# Main.net
KiCad netlist of a schematic drawn in Altium Designer
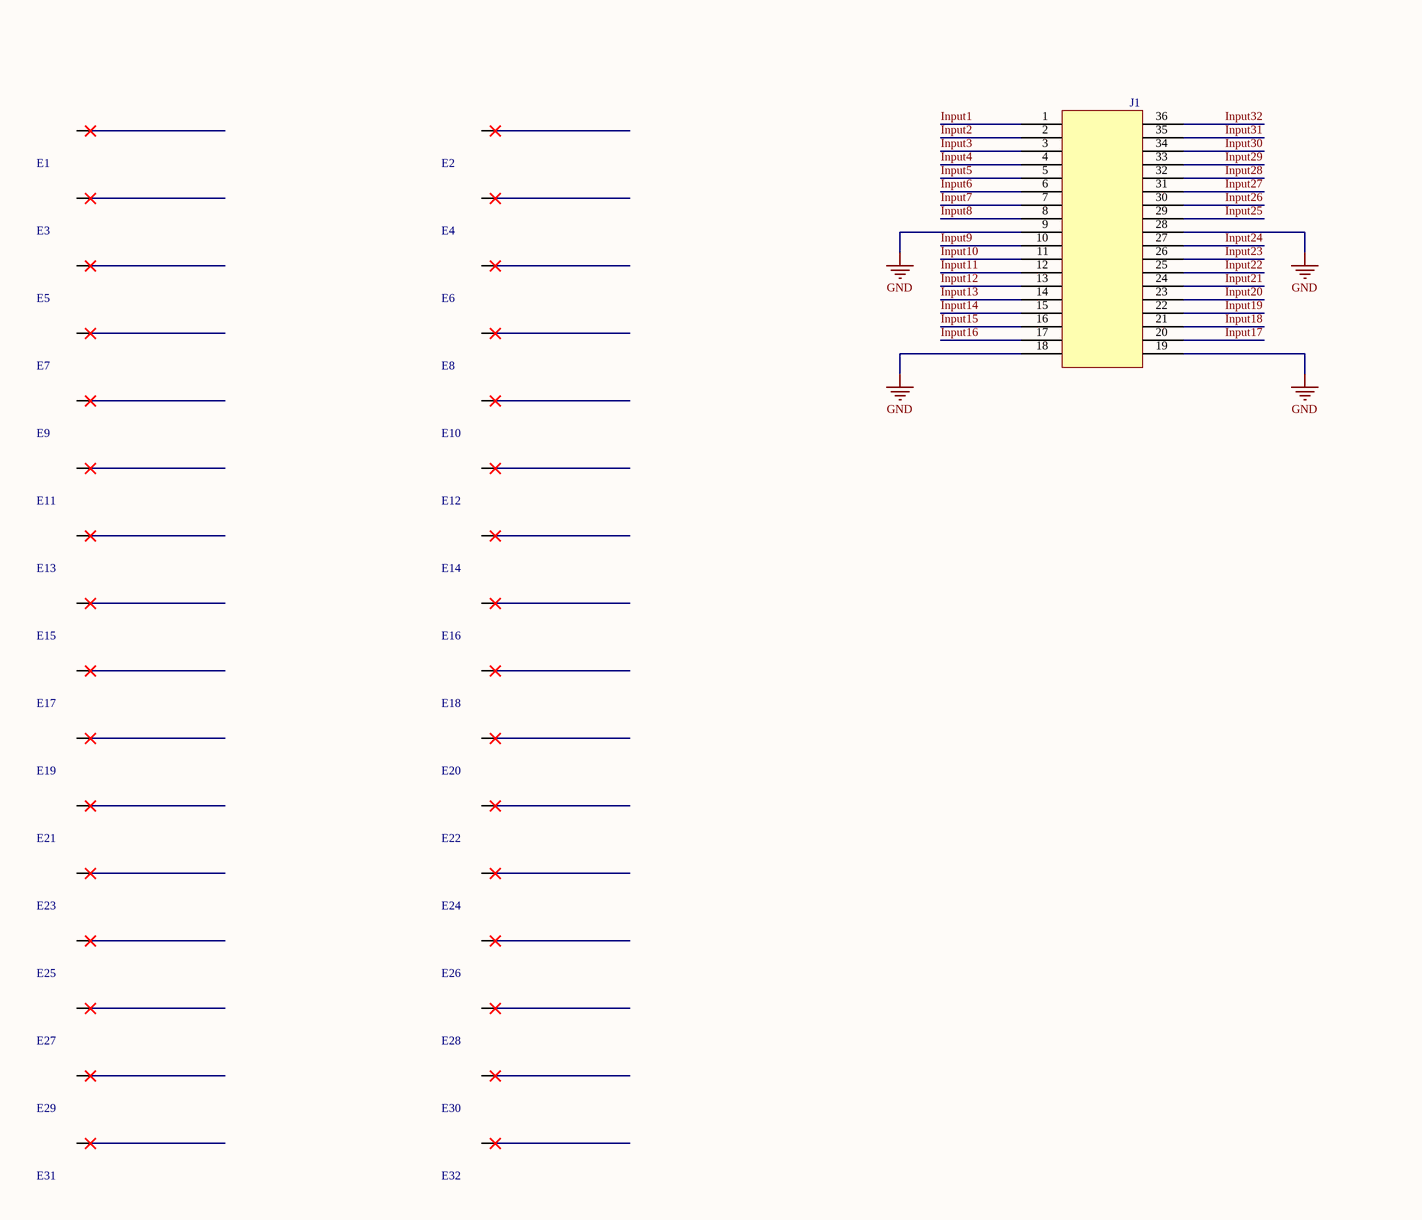
[diagram p0: Main.SchDoc, left]
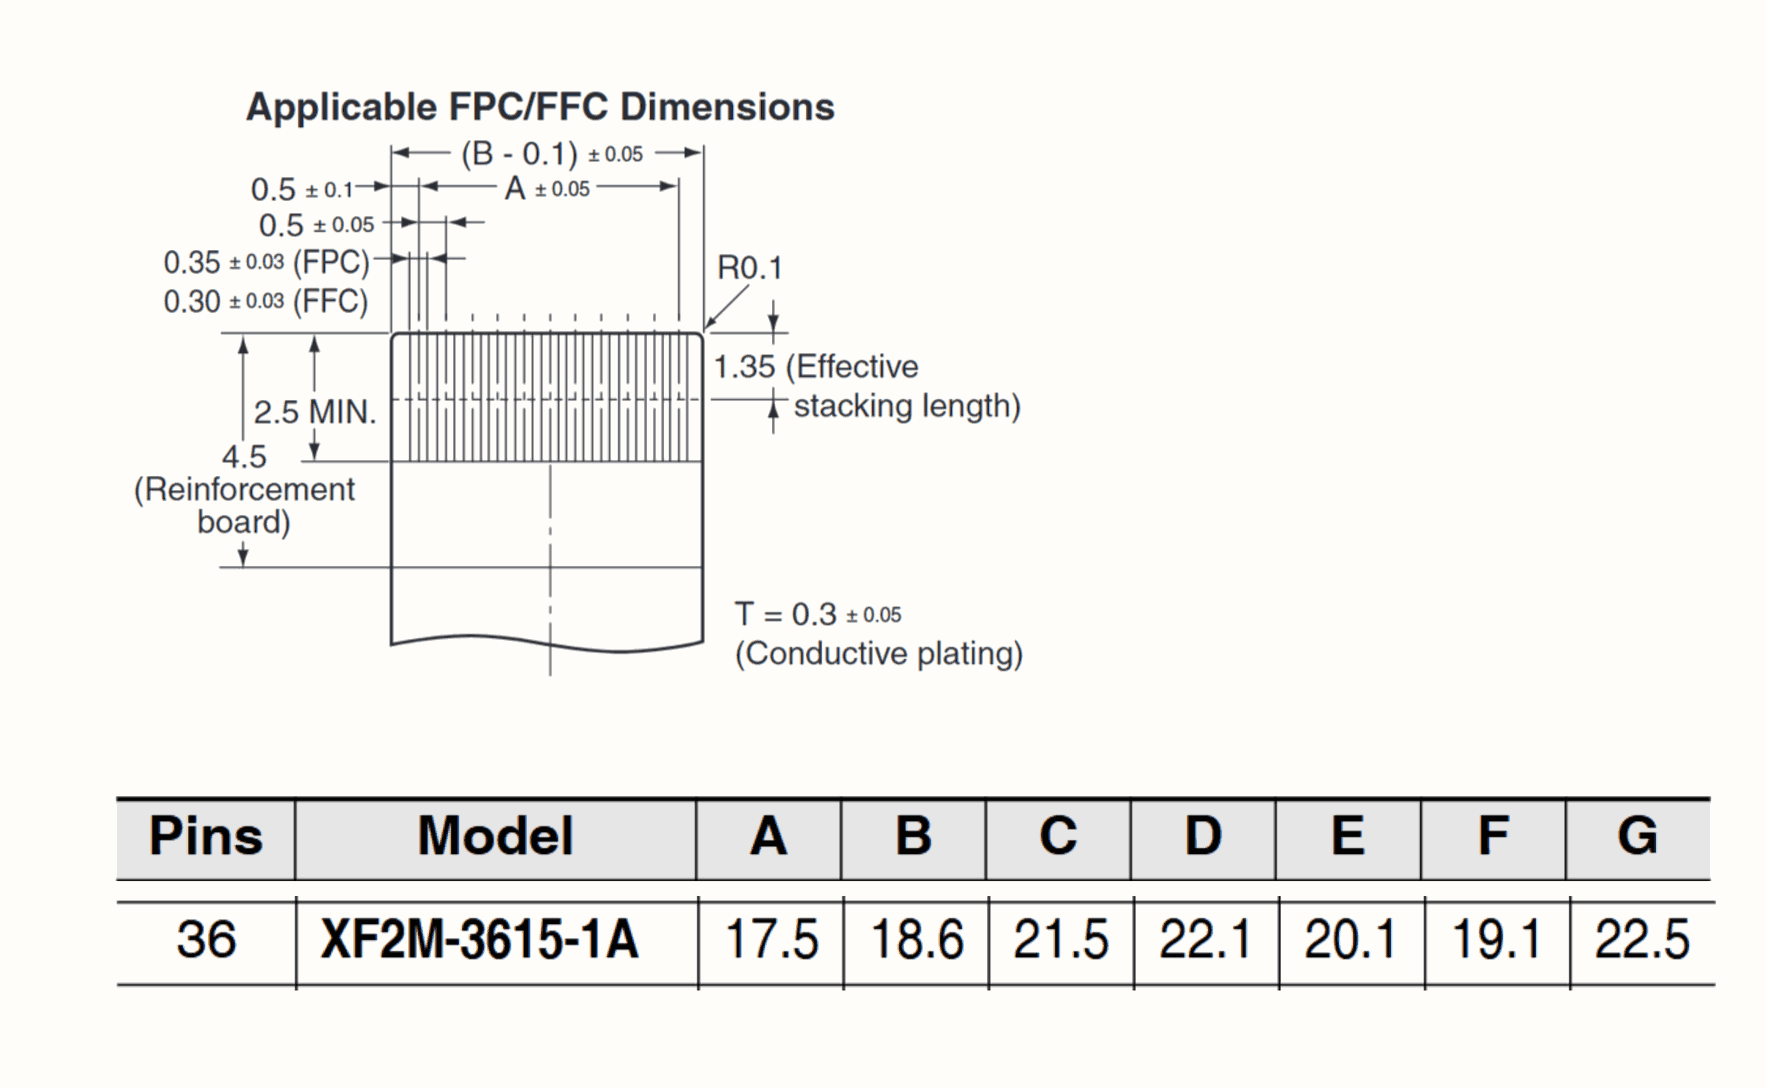
[diagram p1: Main.SchDoc, right]

(export (version "E")
  (design (tool "Eeschema 10.0.6"))
  (components
    (comp (ref "E1")
      (value "2.5 mm")
      (footprint "PCBComponent_1")
      (description "Microneedle electrode - 2.5 mm diameter")
      (libsource (lib "Miscellaneous") (part "SENSE_UNEEDLE"))
    )
    (comp (ref "E2")
      (value "2.5 mm")
      (footprint "PCBComponent_1")
      (description "Microneedle electrode - 2.5 mm diameter")
      (libsource (lib "Miscellaneous") (part "SENSE_UNEEDLE"))
    )
    (comp (ref "E3")
      (value "2.5 mm")
      (footprint "PCBComponent_1")
      (description "Microneedle electrode - 2.5 mm diameter")
      (libsource (lib "Miscellaneous") (part "SENSE_UNEEDLE"))
    )
    (comp (ref "E4")
      (value "2.5 mm")
      (footprint "PCBComponent_1")
      (description "Microneedle electrode - 2.5 mm diameter")
      (libsource (lib "Miscellaneous") (part "SENSE_UNEEDLE"))
    )
    (comp (ref "E5")
      (value "2.5 mm")
      (footprint "PCBComponent_1")
      (description "Microneedle electrode - 2.5 mm diameter")
      (libsource (lib "Miscellaneous") (part "SENSE_UNEEDLE"))
    )
    (comp (ref "E6")
      (value "2.5 mm")
      (footprint "PCBComponent_1")
      (description "Microneedle electrode - 2.5 mm diameter")
      (libsource (lib "Miscellaneous") (part "SENSE_UNEEDLE"))
    )
    (comp (ref "E7")
      (value "2.5 mm")
      (footprint "PCBComponent_1")
      (description "Microneedle electrode - 2.5 mm diameter")
      (libsource (lib "Miscellaneous") (part "SENSE_UNEEDLE"))
    )
    (comp (ref "E8")
      (value "2.5 mm")
      (footprint "PCBComponent_1")
      (description "Microneedle electrode - 2.5 mm diameter")
      (libsource (lib "Miscellaneous") (part "SENSE_UNEEDLE"))
    )
    (comp (ref "E9")
      (value "2.5 mm")
      (footprint "PCBComponent_1")
      (description "Microneedle electrode - 2.5 mm diameter")
      (libsource (lib "Miscellaneous") (part "SENSE_UNEEDLE"))
    )
    (comp (ref "E10")
      (value "2.5 mm")
      (footprint "PCBComponent_1")
      (description "Microneedle electrode - 2.5 mm diameter")
      (libsource (lib "Miscellaneous") (part "SENSE_UNEEDLE"))
    )
    (comp (ref "E11")
      (value "2.5 mm")
      (footprint "PCBComponent_1")
      (description "Microneedle electrode - 2.5 mm diameter")
      (libsource (lib "Miscellaneous") (part "SENSE_UNEEDLE"))
    )
    (comp (ref "E12")
      (value "2.5 mm")
      (footprint "PCBComponent_1")
      (description "Microneedle electrode - 2.5 mm diameter")
      (libsource (lib "Miscellaneous") (part "SENSE_UNEEDLE"))
    )
    (comp (ref "E13")
      (value "2.5 mm")
      (footprint "PCBComponent_1")
      (description "Microneedle electrode - 2.5 mm diameter")
      (libsource (lib "Miscellaneous") (part "SENSE_UNEEDLE"))
    )
    (comp (ref "E14")
      (value "2.5 mm")
      (footprint "PCBComponent_1")
      (description "Microneedle electrode - 2.5 mm diameter")
      (libsource (lib "Miscellaneous") (part "SENSE_UNEEDLE"))
    )
    (comp (ref "E15")
      (value "2.5 mm")
      (footprint "PCBComponent_1")
      (description "Microneedle electrode - 2.5 mm diameter")
      (libsource (lib "Miscellaneous") (part "SENSE_UNEEDLE"))
    )
    (comp (ref "E16")
      (value "2.5 mm")
      (footprint "PCBComponent_1")
      (description "Microneedle electrode - 2.5 mm diameter")
      (libsource (lib "Miscellaneous") (part "SENSE_UNEEDLE"))
    )
    (comp (ref "E17")
      (value "2.5 mm")
      (footprint "PCBComponent_1")
      (description "Microneedle electrode - 2.5 mm diameter")
      (libsource (lib "Miscellaneous") (part "SENSE_UNEEDLE"))
    )
    (comp (ref "E18")
      (value "2.5 mm")
      (footprint "PCBComponent_1")
      (description "Microneedle electrode - 2.5 mm diameter")
      (libsource (lib "Miscellaneous") (part "SENSE_UNEEDLE"))
    )
    (comp (ref "E19")
      (value "2.5 mm")
      (footprint "PCBComponent_1")
      (description "Microneedle electrode - 2.5 mm diameter")
      (libsource (lib "Miscellaneous") (part "SENSE_UNEEDLE"))
    )
    (comp (ref "E20")
      (value "2.5 mm")
      (footprint "PCBComponent_1")
      (description "Microneedle electrode - 2.5 mm diameter")
      (libsource (lib "Miscellaneous") (part "SENSE_UNEEDLE"))
    )
    (comp (ref "E21")
      (value "2.5 mm")
      (footprint "PCBComponent_1")
      (description "Microneedle electrode - 2.5 mm diameter")
      (libsource (lib "Miscellaneous") (part "SENSE_UNEEDLE"))
    )
    (comp (ref "E22")
      (value "2.5 mm")
      (footprint "PCBComponent_1")
      (description "Microneedle electrode - 2.5 mm diameter")
      (libsource (lib "Miscellaneous") (part "SENSE_UNEEDLE"))
    )
    (comp (ref "E23")
      (value "2.5 mm")
      (footprint "PCBComponent_1")
      (description "Microneedle electrode - 2.5 mm diameter")
      (libsource (lib "Miscellaneous") (part "SENSE_UNEEDLE"))
    )
    (comp (ref "E24")
      (value "2.5 mm")
      (footprint "PCBComponent_1")
      (description "Microneedle electrode - 2.5 mm diameter")
      (libsource (lib "Miscellaneous") (part "SENSE_UNEEDLE"))
    )
    (comp (ref "E25")
      (value "2.5 mm")
      (footprint "PCBComponent_1")
      (description "Microneedle electrode - 2.5 mm diameter")
      (libsource (lib "Miscellaneous") (part "SENSE_UNEEDLE"))
    )
    (comp (ref "E26")
      (value "2.5 mm")
      (footprint "PCBComponent_1")
      (description "Microneedle electrode - 2.5 mm diameter")
      (libsource (lib "Miscellaneous") (part "SENSE_UNEEDLE"))
    )
    (comp (ref "E27")
      (value "2.5 mm")
      (footprint "PCBComponent_1")
      (description "Microneedle electrode - 2.5 mm diameter")
      (libsource (lib "Miscellaneous") (part "SENSE_UNEEDLE"))
    )
    (comp (ref "E28")
      (value "2.5 mm")
      (footprint "PCBComponent_1")
      (description "Microneedle electrode - 2.5 mm diameter")
      (libsource (lib "Miscellaneous") (part "SENSE_UNEEDLE"))
    )
    (comp (ref "E29")
      (value "2.5 mm")
      (footprint "PCBComponent_1")
      (description "Microneedle electrode - 2.5 mm diameter")
      (libsource (lib "Miscellaneous") (part "SENSE_UNEEDLE"))
    )
    (comp (ref "E30")
      (value "2.5 mm")
      (footprint "PCBComponent_1")
      (description "Microneedle electrode - 2.5 mm diameter")
      (libsource (lib "Miscellaneous") (part "SENSE_UNEEDLE"))
    )
    (comp (ref "E31")
      (value "2.5 mm")
      (footprint "PCBComponent_1")
      (description "Microneedle electrode - 2.5 mm diameter")
      (libsource (lib "Miscellaneous") (part "SENSE_UNEEDLE"))
    )
    (comp (ref "E32")
      (value "2.5 mm")
      (footprint "PCBComponent_1")
      (description "Microneedle electrode - 2.5 mm diameter")
      (libsource (lib "Miscellaneous") (part "SENSE_UNEEDLE"))
    )
    (comp (ref "J1")
      (value "XF2M-3615-1A")
      (footprint "CONN_FPC_2X18_0MM5")
      (description "FPC Connector - FPC Side. 0.5 mm pitch\r\nCompatible with XF2M-3615-1A")
      (libsource (lib "Connectors") (part "CONN_FPC_2X18_0MM5"))
    )
  )
  (nets
    (net (code "1") (name "/Input1") (class "Default")
      (node (ref "J1") (pin "1") (pinfunction "1_1") (pintype "passive"))
    )
    (net (code "2") (name "/Input2") (class "Default")
      (node (ref "J1") (pin "2") (pinfunction "2_2") (pintype "passive"))
    )
    (net (code "3") (name "/Input3") (class "Default")
      (node (ref "J1") (pin "3") (pinfunction "3_3") (pintype "passive"))
    )
    (net (code "4") (name "/Input4") (class "Default")
      (node (ref "J1") (pin "4") (pinfunction "4_4") (pintype "passive"))
    )
    (net (code "5") (name "/Input5") (class "Default")
      (node (ref "J1") (pin "5") (pinfunction "5_5") (pintype "passive"))
    )
    (net (code "6") (name "/Input6") (class "Default")
      (node (ref "J1") (pin "6") (pinfunction "6_6") (pintype "passive"))
    )
    (net (code "7") (name "/Input7") (class "Default")
      (node (ref "J1") (pin "7") (pinfunction "7_7") (pintype "passive"))
    )
    (net (code "8") (name "/Input8") (class "Default")
      (node (ref "J1") (pin "8") (pinfunction "8_8") (pintype "passive"))
    )
    (net (code "9") (name "/Input9") (class "Default")
      (node (ref "J1") (pin "10") (pinfunction "10_10") (pintype "passive"))
    )
    (net (code "10") (name "/Input10") (class "Default")
      (node (ref "J1") (pin "11") (pinfunction "11_11") (pintype "passive"))
    )
    (net (code "11") (name "/Input11") (class "Default")
      (node (ref "J1") (pin "12") (pinfunction "12_12") (pintype "passive"))
    )
    (net (code "12") (name "/Input12") (class "Default")
      (node (ref "J1") (pin "13") (pinfunction "13_13") (pintype "passive"))
    )
    (net (code "13") (name "/Input13") (class "Default")
      (node (ref "J1") (pin "14") (pinfunction "14_14") (pintype "passive"))
    )
    (net (code "14") (name "/Input14") (class "Default")
      (node (ref "J1") (pin "15") (pinfunction "15_15") (pintype "passive"))
    )
    (net (code "15") (name "/Input15") (class "Default")
      (node (ref "J1") (pin "16") (pinfunction "16_16") (pintype "passive"))
    )
    (net (code "16") (name "/Input16") (class "Default")
      (node (ref "J1") (pin "17") (pinfunction "17_17") (pintype "passive"))
    )
    (net (code "17") (name "/Input17") (class "Default")
      (node (ref "J1") (pin "20") (pinfunction "20_20") (pintype "passive"))
    )
    (net (code "18") (name "/Input18") (class "Default")
      (node (ref "J1") (pin "21") (pinfunction "21_21") (pintype "passive"))
    )
    (net (code "19") (name "/Input19") (class "Default")
      (node (ref "J1") (pin "22") (pinfunction "22_22") (pintype "passive"))
    )
    (net (code "20") (name "/Input20") (class "Default")
      (node (ref "J1") (pin "23") (pinfunction "23_23") (pintype "passive"))
    )
    (net (code "21") (name "/Input21") (class "Default")
      (node (ref "J1") (pin "24") (pinfunction "24_24") (pintype "passive"))
    )
    (net (code "22") (name "/Input22") (class "Default")
      (node (ref "J1") (pin "25") (pinfunction "25_25") (pintype "passive"))
    )
    (net (code "23") (name "/Input23") (class "Default")
      (node (ref "J1") (pin "26") (pinfunction "26_26") (pintype "passive"))
    )
    (net (code "24") (name "/Input24") (class "Default")
      (node (ref "J1") (pin "27") (pinfunction "27_27") (pintype "passive"))
    )
    (net (code "25") (name "/Input25") (class "Default")
      (node (ref "J1") (pin "29") (pinfunction "29_29") (pintype "passive"))
    )
    (net (code "26") (name "/Input26") (class "Default")
      (node (ref "J1") (pin "30") (pinfunction "30_30") (pintype "passive"))
    )
    (net (code "27") (name "/Input27") (class "Default")
      (node (ref "J1") (pin "31") (pinfunction "31_31") (pintype "passive"))
    )
    (net (code "28") (name "/Input28") (class "Default")
      (node (ref "J1") (pin "32") (pinfunction "32_32") (pintype "passive"))
    )
    (net (code "29") (name "/Input29") (class "Default")
      (node (ref "J1") (pin "33") (pinfunction "33_33") (pintype "passive"))
    )
    (net (code "30") (name "/Input30") (class "Default")
      (node (ref "J1") (pin "34") (pinfunction "34_34") (pintype "passive"))
    )
    (net (code "31") (name "/Input31") (class "Default")
      (node (ref "J1") (pin "35") (pinfunction "35_35") (pintype "passive"))
    )
    (net (code "32") (name "/Input32") (class "Default")
      (node (ref "J1") (pin "36") (pinfunction "36_36") (pintype "passive"))
    )
    (net (code "33") (name "GND") (class "Default")
      (node (ref "J1") (pin "18") (pinfunction "18_18") (pintype "passive"))
      (node (ref "J1") (pin "19") (pinfunction "19_19") (pintype "passive"))
      (node (ref "J1") (pin "28") (pinfunction "28_28") (pintype "passive"))
      (node (ref "J1") (pin "9") (pinfunction "9_9") (pintype "passive"))
    )
    (net (code "34") (name "unconnected-(E1-E-Pad1)") (class "Default")
      (node (ref "E1") (pin "1") (pinfunction "E_1") (pintype "passive+no_connect"))
    )
    (net (code "35") (name "unconnected-(E2-E-Pad1)") (class "Default")
      (node (ref "E2") (pin "1") (pinfunction "E_1") (pintype "passive+no_connect"))
    )
    (net (code "36") (name "unconnected-(E3-E-Pad1)") (class "Default")
      (node (ref "E3") (pin "1") (pinfunction "E_1") (pintype "passive+no_connect"))
    )
    (net (code "37") (name "unconnected-(E4-E-Pad1)") (class "Default")
      (node (ref "E4") (pin "1") (pinfunction "E_1") (pintype "passive+no_connect"))
    )
    (net (code "38") (name "unconnected-(E5-E-Pad1)") (class "Default")
      (node (ref "E5") (pin "1") (pinfunction "E_1") (pintype "passive+no_connect"))
    )
    (net (code "39") (name "unconnected-(E6-E-Pad1)") (class "Default")
      (node (ref "E6") (pin "1") (pinfunction "E_1") (pintype "passive+no_connect"))
    )
    (net (code "40") (name "unconnected-(E7-E-Pad1)") (class "Default")
      (node (ref "E7") (pin "1") (pinfunction "E_1") (pintype "passive+no_connect"))
    )
    (net (code "41") (name "unconnected-(E8-E-Pad1)") (class "Default")
      (node (ref "E8") (pin "1") (pinfunction "E_1") (pintype "passive+no_connect"))
    )
    (net (code "42") (name "unconnected-(E9-E-Pad1)") (class "Default")
      (node (ref "E9") (pin "1") (pinfunction "E_1") (pintype "passive+no_connect"))
    )
    (net (code "43") (name "unconnected-(E10-E-Pad1)") (class "Default")
      (node (ref "E10") (pin "1") (pinfunction "E_1") (pintype "passive+no_connect"))
    )
    (net (code "44") (name "unconnected-(E11-E-Pad1)") (class "Default")
      (node (ref "E11") (pin "1") (pinfunction "E_1") (pintype "passive+no_connect"))
    )
    (net (code "45") (name "unconnected-(E12-E-Pad1)") (class "Default")
      (node (ref "E12") (pin "1") (pinfunction "E_1") (pintype "passive+no_connect"))
    )
    (net (code "46") (name "unconnected-(E13-E-Pad1)") (class "Default")
      (node (ref "E13") (pin "1") (pinfunction "E_1") (pintype "passive+no_connect"))
    )
    (net (code "47") (name "unconnected-(E14-E-Pad1)") (class "Default")
      (node (ref "E14") (pin "1") (pinfunction "E_1") (pintype "passive+no_connect"))
    )
    (net (code "48") (name "unconnected-(E15-E-Pad1)") (class "Default")
      (node (ref "E15") (pin "1") (pinfunction "E_1") (pintype "passive+no_connect"))
    )
    (net (code "49") (name "unconnected-(E16-E-Pad1)") (class "Default")
      (node (ref "E16") (pin "1") (pinfunction "E_1") (pintype "passive+no_connect"))
    )
    (net (code "50") (name "unconnected-(E17-E-Pad1)") (class "Default")
      (node (ref "E17") (pin "1") (pinfunction "E_1") (pintype "passive+no_connect"))
    )
    (net (code "51") (name "unconnected-(E18-E-Pad1)") (class "Default")
      (node (ref "E18") (pin "1") (pinfunction "E_1") (pintype "passive+no_connect"))
    )
    (net (code "52") (name "unconnected-(E19-E-Pad1)") (class "Default")
      (node (ref "E19") (pin "1") (pinfunction "E_1") (pintype "passive+no_connect"))
    )
    (net (code "53") (name "unconnected-(E20-E-Pad1)") (class "Default")
      (node (ref "E20") (pin "1") (pinfunction "E_1") (pintype "passive+no_connect"))
    )
    (net (code "54") (name "unconnected-(E21-E-Pad1)") (class "Default")
      (node (ref "E21") (pin "1") (pinfunction "E_1") (pintype "passive+no_connect"))
    )
    (net (code "55") (name "unconnected-(E22-E-Pad1)") (class "Default")
      (node (ref "E22") (pin "1") (pinfunction "E_1") (pintype "passive+no_connect"))
    )
    (net (code "56") (name "unconnected-(E23-E-Pad1)") (class "Default")
      (node (ref "E23") (pin "1") (pinfunction "E_1") (pintype "passive+no_connect"))
    )
    (net (code "57") (name "unconnected-(E24-E-Pad1)") (class "Default")
      (node (ref "E24") (pin "1") (pinfunction "E_1") (pintype "passive+no_connect"))
    )
    (net (code "58") (name "unconnected-(E25-E-Pad1)") (class "Default")
      (node (ref "E25") (pin "1") (pinfunction "E_1") (pintype "passive+no_connect"))
    )
    (net (code "59") (name "unconnected-(E26-E-Pad1)") (class "Default")
      (node (ref "E26") (pin "1") (pinfunction "E_1") (pintype "passive+no_connect"))
    )
    (net (code "60") (name "unconnected-(E27-E-Pad1)") (class "Default")
      (node (ref "E27") (pin "1") (pinfunction "E_1") (pintype "passive+no_connect"))
    )
    (net (code "61") (name "unconnected-(E28-E-Pad1)") (class "Default")
      (node (ref "E28") (pin "1") (pinfunction "E_1") (pintype "passive+no_connect"))
    )
    (net (code "62") (name "unconnected-(E29-E-Pad1)") (class "Default")
      (node (ref "E29") (pin "1") (pinfunction "E_1") (pintype "passive+no_connect"))
    )
    (net (code "63") (name "unconnected-(E30-E-Pad1)") (class "Default")
      (node (ref "E30") (pin "1") (pinfunction "E_1") (pintype "passive+no_connect"))
    )
    (net (code "64") (name "unconnected-(E31-E-Pad1)") (class "Default")
      (node (ref "E31") (pin "1") (pinfunction "E_1") (pintype "passive+no_connect"))
    )
    (net (code "65") (name "unconnected-(E32-E-Pad1)") (class "Default")
      (node (ref "E32") (pin "1") (pinfunction "E_1") (pintype "passive+no_connect"))
    )
  )
)
